# signal_generator_PCB.net
KiCad netlist of a schematic drawn in EAGLE
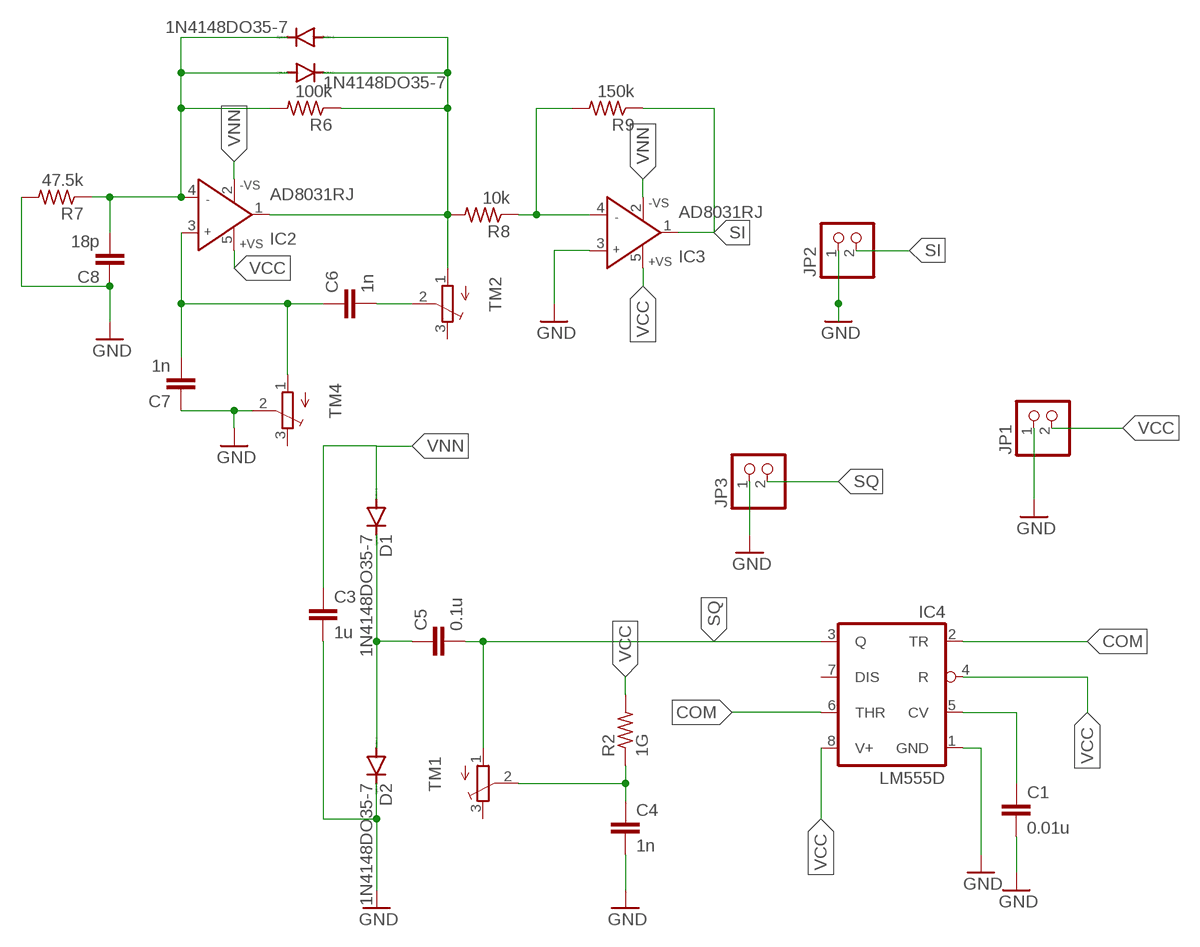
[diagram p0: schematic, sheet 1]

(export (version "E")
  (design (tool "Eeschema 10.0.6"))
  (components
    (comp (ref "C1")
      (value "0.01u")
      (footprint "eagle-import:C0805")
      (libsource (lib "eagle-import") (part "C-EUC0805"))
    )
    (comp (ref "C3")
      (value "1u")
      (footprint "eagle-import:C0805")
      (libsource (lib "eagle-import") (part "C-EUC0805"))
    )
    (comp (ref "C4")
      (value "1n")
      (footprint "eagle-import:C0805")
      (libsource (lib "eagle-import") (part "C-EUC0805"))
    )
    (comp (ref "C5")
      (value "0.1u")
      (footprint "eagle-import:C0805")
      (libsource (lib "eagle-import") (part "C-EUC0805"))
    )
    (comp (ref "C6")
      (value "1n")
      (footprint "eagle-import:C0805")
      (libsource (lib "eagle-import") (part "C-EUC0805"))
    )
    (comp (ref "C7")
      (value "1n")
      (footprint "eagle-import:C0805")
      (libsource (lib "eagle-import") (part "C-EUC0805"))
    )
    (comp (ref "C8")
      (value "18p")
      (footprint "eagle-import:C0805")
      (libsource (lib "eagle-import") (part "C-EUC0805"))
    )
    (comp (ref "D1")
      (value "1N4148DO35-7")
      (footprint "eagle-import:DO35-7")
      (libsource (lib "eagle-import") (part "1N4148DO35-7"))
    )
    (comp (ref "D2")
      (value "1N4148DO35-7")
      (footprint "eagle-import:DO35-7")
      (libsource (lib "eagle-import") (part "1N4148DO35-7"))
    )
    (comp (ref "D3")
      (value "1N4148DO35-7")
      (footprint "eagle-import:DO35-7")
      (libsource (lib "eagle-import") (part "1N4148DO35-7"))
    )
    (comp (ref "D4")
      (value "1N4148DO35-7")
      (footprint "eagle-import:DO35-7")
      (libsource (lib "eagle-import") (part "1N4148DO35-7"))
    )
    (comp (ref "IC2")
      (value "AD8031RJ")
      (footprint "eagle-import:SOT23-5")
      (fields (field (name "MPN") "AD8031ARTZ-REEL7"))
      (libsource (lib "eagle-import") (part "AD8031RJ"))
    )
    (comp (ref "IC3")
      (value "AD8031RJ")
      (footprint "eagle-import:SOT23-5")
      (fields (field (name "MPN") "AD8031ARTZ-REEL7"))
      (libsource (lib "eagle-import") (part "AD8031RJ"))
    )
    (comp (ref "IC4")
      (value "LM555D")
      (footprint "eagle-import:SO08")
      (libsource (lib "eagle-import") (part "555DLM"))
    )
    (comp (ref "JP1")
      (value "PINHD-1X2")
      (footprint "eagle-import:1X02")
      (libsource (lib "eagle-import") (part "PINHD-1X2"))
    )
    (comp (ref "JP2")
      (value "PINHD-1X2")
      (footprint "eagle-import:1X02")
      (libsource (lib "eagle-import") (part "PINHD-1X2"))
    )
    (comp (ref "JP3")
      (value "PINHD-1X2")
      (footprint "eagle-import:1X02")
      (libsource (lib "eagle-import") (part "PINHD-1X2"))
    )
    (comp (ref "R2")
      (value "1G")
      (footprint "eagle-import:M0805")
      (libsource (lib "eagle-import") (part "R-US_M0805"))
    )
    (comp (ref "R6")
      (value "100k")
      (footprint "eagle-import:M0805")
      (libsource (lib "eagle-import") (part "R-US_M0805"))
    )
    (comp (ref "R7")
      (value "47.5k")
      (footprint "eagle-import:M0805")
      (libsource (lib "eagle-import") (part "R-US_M0805"))
    )
    (comp (ref "R8")
      (value "10k")
      (footprint "eagle-import:M0805")
      (libsource (lib "eagle-import") (part "R-US_M0805"))
    )
    (comp (ref "R9")
      (value "150k")
      (footprint "eagle-import:M0805")
      (libsource (lib "eagle-import") (part "R-US_M0805"))
    )
    (comp (ref "TM1")
      (value "TRIMPOTTC33X")
      (footprint "eagle-import:TC33X")
      (libsource (lib "eagle-import") (part "TRIMPOTTC33X"))
    )
    (comp (ref "TM2")
      (value "TRIMPOTTC33X")
      (footprint "eagle-import:TC33X")
      (libsource (lib "eagle-import") (part "TRIMPOTTC33X"))
    )
    (comp (ref "TM4")
      (value "TRIMPOTTC33X")
      (footprint "eagle-import:TC33X")
      (libsource (lib "eagle-import") (part "TRIMPOTTC33X"))
    )
  )
  (nets
    (net (code "1") (name "COM") (class "Default")
      (node (ref "IC4") (pin "2") (pinfunction "TR_2") (pintype "input"))
      (node (ref "IC4") (pin "6") (pinfunction "THR_6") (pintype "input"))
    )
    (net (code "2") (name "GND") (class "Default")
      (node (ref "C1") (pin "2") (pinfunction "2_2") (pintype "passive"))
      (node (ref "C3") (pin "2") (pinfunction "2_2") (pintype "passive"))
      (node (ref "C4") (pin "2") (pinfunction "2_2") (pintype "passive"))
      (node (ref "C7") (pin "1") (pinfunction "1_1") (pintype "passive"))
      (node (ref "C8") (pin "1") (pinfunction "1_1") (pintype "passive"))
      (node (ref "D2") (pin "C") (pinfunction "C_C") (pintype "passive"))
      (node (ref "IC3") (pin "3") (pinfunction "IN+_3") (pintype "input"))
      (node (ref "IC4") (pin "1") (pinfunction "GND_1") (pintype "power_in"))
      (node (ref "JP1") (pin "1") (pinfunction "1_1") (pintype "passive"))
      (node (ref "JP2") (pin "1") (pinfunction "1_1") (pintype "passive"))
      (node (ref "JP3") (pin "1") (pinfunction "1_1") (pintype "passive"))
      (node (ref "R7") (pin "2") (pinfunction "2_2") (pintype "passive"))
      (node (ref "TM4") (pin "2") (pinfunction "S_2") (pintype "passive"))
    )
    (net (code "3") (name "Net-(C5-Pad1)") (class "Default")
      (node (ref "C5") (pin "1") (pinfunction "1_1") (pintype "passive"))
      (node (ref "D1") (pin "C") (pinfunction "C_C") (pintype "passive"))
      (node (ref "D2") (pin "A") (pinfunction "A_A") (pintype "passive"))
    )
    (net (code "4") (name "Net-(IC2-IN+)") (class "Default")
      (node (ref "C6") (pin "1") (pinfunction "1_1") (pintype "passive"))
      (node (ref "C7") (pin "2") (pinfunction "2_2") (pintype "passive"))
      (node (ref "IC2") (pin "3") (pinfunction "IN+_3") (pintype "input"))
      (node (ref "TM4") (pin "1") (pinfunction "A_1") (pintype "passive"))
    )
    (net (code "5") (name "Net-(IC2-IN-)") (class "Default")
      (node (ref "C8") (pin "2") (pinfunction "2_2") (pintype "passive"))
      (node (ref "D3") (pin "A") (pinfunction "A_A") (pintype "passive"))
      (node (ref "D4") (pin "C") (pinfunction "C_C") (pintype "passive"))
      (node (ref "IC2") (pin "4") (pinfunction "IN-_4") (pintype "input"))
      (node (ref "R6") (pin "2") (pinfunction "2_2") (pintype "passive"))
      (node (ref "R7") (pin "1") (pinfunction "1_1") (pintype "passive"))
    )
    (net (code "6") (name "Net-(IC2-OUT)") (class "Default")
      (node (ref "D3") (pin "C") (pinfunction "C_C") (pintype "passive"))
      (node (ref "D4") (pin "A") (pinfunction "A_A") (pintype "passive"))
      (node (ref "IC2") (pin "1") (pinfunction "OUT_1") (pintype "output"))
      (node (ref "R6") (pin "1") (pinfunction "1_1") (pintype "passive"))
      (node (ref "R8") (pin "2") (pinfunction "2_2") (pintype "passive"))
      (node (ref "TM2") (pin "1") (pinfunction "A_1") (pintype "passive"))
    )
    (net (code "7") (name "Net-(IC3-IN-)") (class "Default")
      (node (ref "IC3") (pin "4") (pinfunction "IN-_4") (pintype "input"))
      (node (ref "R8") (pin "1") (pinfunction "1_1") (pintype "passive"))
      (node (ref "R9") (pin "2") (pinfunction "2_2") (pintype "passive"))
    )
    (net (code "8") (name "Net-(IC4-CV)") (class "Default")
      (node (ref "C1") (pin "1") (pinfunction "1_1") (pintype "passive"))
      (node (ref "IC4") (pin "5") (pinfunction "CV_5") (pintype "input"))
    )
    (net (code "9") (name "Net-(TM1-S)") (class "Default")
      (node (ref "C4") (pin "1") (pinfunction "1_1") (pintype "passive"))
      (node (ref "R2") (pin "1") (pinfunction "1_1") (pintype "passive"))
      (node (ref "TM1") (pin "2") (pinfunction "S_2") (pintype "passive"))
    )
    (net (code "10") (name "Net-(TM2-S)") (class "Default")
      (node (ref "C6") (pin "2") (pinfunction "2_2") (pintype "passive"))
      (node (ref "TM2") (pin "2") (pinfunction "S_2") (pintype "passive"))
    )
    (net (code "11") (name "SI") (class "Default")
      (node (ref "IC3") (pin "1") (pinfunction "OUT_1") (pintype "output"))
      (node (ref "JP2") (pin "2") (pinfunction "2_2") (pintype "passive"))
      (node (ref "R9") (pin "1") (pinfunction "1_1") (pintype "passive"))
    )
    (net (code "12") (name "SQ") (class "Default")
      (node (ref "C5") (pin "2") (pinfunction "2_2") (pintype "passive"))
      (node (ref "IC4") (pin "3") (pinfunction "Q_3") (pintype "output"))
      (node (ref "JP3") (pin "2") (pinfunction "2_2") (pintype "passive"))
      (node (ref "TM1") (pin "1") (pinfunction "A_1") (pintype "passive"))
    )
    (net (code "13") (name "VCC") (class "Default")
      (node (ref "IC2") (pin "5") (pinfunction "+VS_5") (pintype "input"))
      (node (ref "IC3") (pin "5") (pinfunction "+VS_5") (pintype "input"))
      (node (ref "IC4") (pin "4") (pinfunction "R_4") (pintype "input"))
      (node (ref "IC4") (pin "8") (pinfunction "V+_8") (pintype "power_in"))
      (node (ref "JP1") (pin "2") (pinfunction "2_2") (pintype "passive"))
      (node (ref "R2") (pin "2") (pinfunction "2_2") (pintype "passive"))
    )
    (net (code "14") (name "VNN") (class "Default")
      (node (ref "C3") (pin "1") (pinfunction "1_1") (pintype "passive"))
      (node (ref "D1") (pin "A") (pinfunction "A_A") (pintype "passive"))
      (node (ref "IC2") (pin "2") (pinfunction "-VS_2") (pintype "input"))
      (node (ref "IC3") (pin "2") (pinfunction "-VS_2") (pintype "input"))
    )
    (net (code "15") (name "unconnected-(IC4-DIS-Pad7)") (class "Default")
      (node (ref "IC4") (pin "7") (pinfunction "DIS_7") (pintype "input"))
    )
    (net (code "16") (name "unconnected-(TM1-E-Pad3)") (class "Default")
      (node (ref "TM1") (pin "3") (pinfunction "E_3") (pintype "passive"))
    )
    (net (code "17") (name "unconnected-(TM2-E-Pad3)") (class "Default")
      (node (ref "TM2") (pin "3") (pinfunction "E_3") (pintype "passive"))
    )
    (net (code "18") (name "unconnected-(TM4-E-Pad3)") (class "Default")
      (node (ref "TM4") (pin "3") (pinfunction "E_3") (pintype "passive"))
    )
  )
)
